# ASD2205.net
KiCad netlist of a schematic drawn in EAGLE
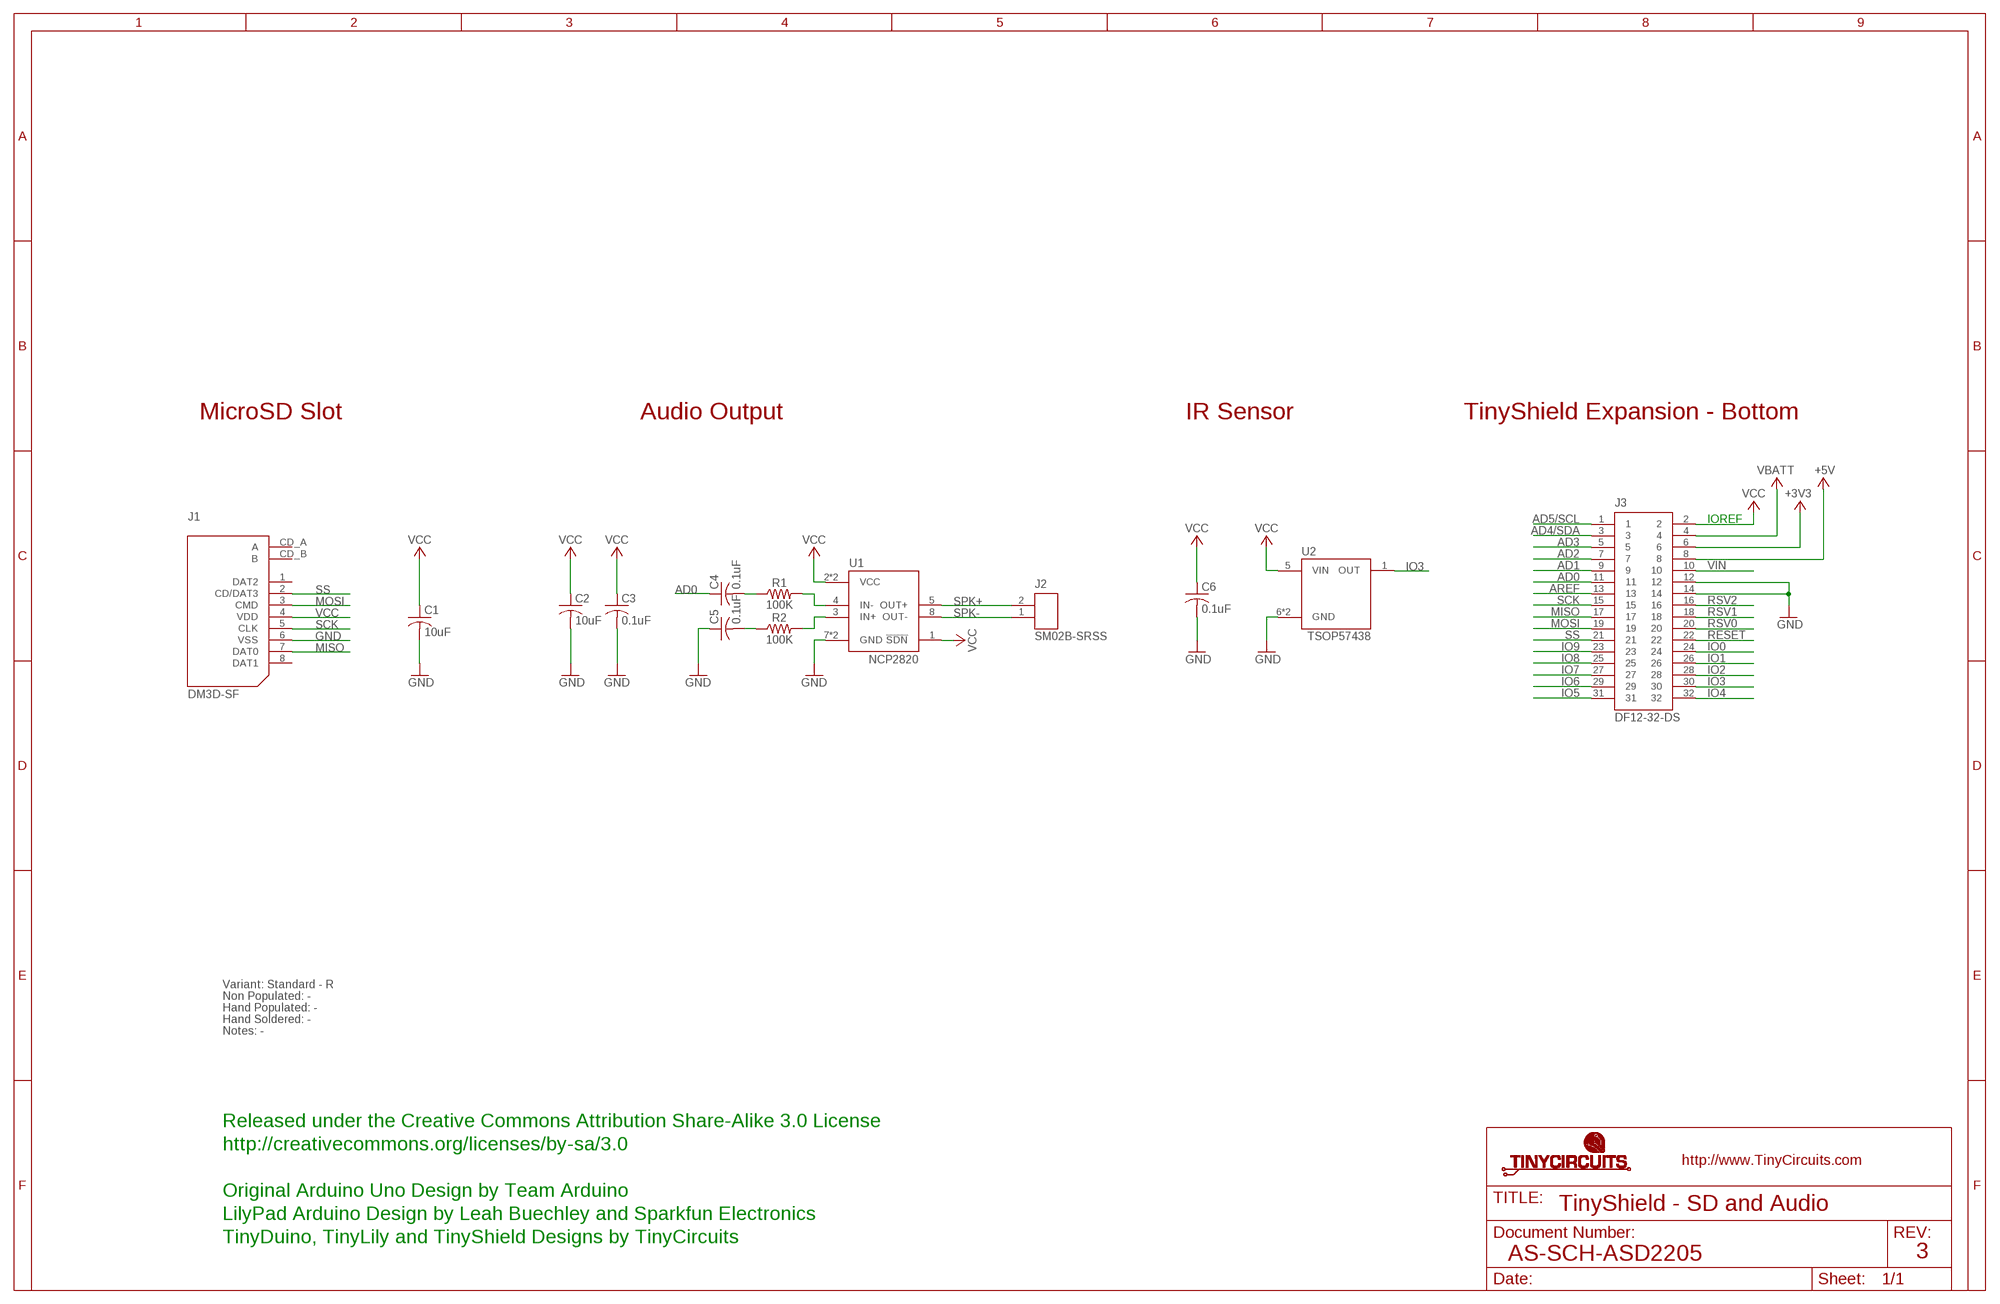
[diagram p0: schematic, sheet 1]

(export (version "E")
  (design (tool "Eeschema 10.0.6"))
  (components
    (comp (ref "C1")
      (value "10uF")
      (footprint "eagle-import:C0603")
      (fields (field (name "PARTNO") "AS-ITM-00002"))
      (libsource (lib "eagle-import") (part "AS-ITM-00002"))
    )
    (comp (ref "C2")
      (value "10uF")
      (footprint "eagle-import:C0603")
      (fields (field (name "PARTNO") "AS-ITM-00002") (field (name "PARTNO_1") "AS-ITM-00002"))
      (libsource (lib "eagle-import") (part "AS-ITM-00002"))
    )
    (comp (ref "C3")
      (value "0.1uF")
      (footprint "eagle-import:C0402")
      (fields (field (name "PARTNO") "AS-ITM-00008"))
      (libsource (lib "eagle-import") (part "AS-ITM-00008"))
    )
    (comp (ref "C4")
      (value "0.1uF")
      (footprint "eagle-import:C0402")
      (fields (field (name "PARTNO") "AS-ITM-00008"))
      (libsource (lib "eagle-import") (part "AS-ITM-00008"))
    )
    (comp (ref "C5")
      (value "0.1uF")
      (footprint "eagle-import:C0402")
      (fields (field (name "PARTNO") "AS-ITM-00008"))
      (libsource (lib "eagle-import") (part "AS-ITM-00008"))
    )
    (comp (ref "C6")
      (value "0.1uF")
      (footprint "eagle-import:C0402")
      (fields (field (name "PARTNO") "AS-ITM-00008"))
      (libsource (lib "eagle-import") (part "AS-ITM-00008"))
    )
    (comp (ref "J1")
      (value "DM3D-SF")
      (footprint "eagle-import:SD_CARD")
      (fields (field (name "PARTNO") "AS-ITM-00047"))
      (libsource (lib "eagle-import") (part "AS-ITM-00047"))
    )
    (comp (ref "J2")
      (value "SM02B-SRSS")
      (footprint "eagle-import:JST_SH_2X1")
      (fields (field (name "PARTNO") "AS-ITM-00231"))
      (libsource (lib "eagle-import") (part "AS-ITM-00231"))
    )
    (comp (ref "J3")
      (value "DF12-32-DS")
      (footprint "eagle-import:DF12-32-DS")
      (fields (field (name "PARTNO") "AS-ITM-00012") (field (name "PARTNO_1") "AS-ITM-00012"))
      (libsource (lib "eagle-import") (part "AS-ITM-00012"))
    )
    (comp (ref "R1")
      (value "100K")
      (footprint "eagle-import:0402")
      (fields (field (name "PARTNO") "AS-ITM-00004"))
      (libsource (lib "eagle-import") (part "AS-ITM-00004"))
    )
    (comp (ref "R2")
      (value "100K")
      (footprint "eagle-import:0402")
      (fields (field (name "PARTNO") "AS-ITM-00004"))
      (libsource (lib "eagle-import") (part "AS-ITM-00004"))
    )
    (comp (ref "U1")
      (value "NCP2820")
      (footprint "eagle-import:WSON-8")
      (fields (field (name "PARTNO") "AS-ITM-00370"))
      (libsource (lib "eagle-import") (part "AS-ITM-00370"))
    )
    (comp (ref "U2")
      (value "TSOP57438")
      (footprint "eagle-import:TSOP57")
      (fields (field (name "PARTNO") "AS-ITM-00360"))
      (libsource (lib "eagle-import") (part "AS-ITM-00360"))
    )
  )
  (nets
    (net (code "1") (name "+3V3") (class "Default")
      (node (ref "J3") (pin "6") (pinfunction "6_6") (pintype "bidirectional"))
    )
    (net (code "2") (name "+5V") (class "Default")
      (node (ref "J3") (pin "8") (pinfunction "8_8") (pintype "bidirectional"))
    )
    (net (code "3") (name "/AD0") (class "Default")
      (node (ref "C4") (pin "1") (pinfunction "1_1") (pintype "passive"))
      (node (ref "J3") (pin "11") (pinfunction "11_11") (pintype "bidirectional"))
    )
    (net (code "4") (name "/AD1") (class "Default")
      (node (ref "J3") (pin "9") (pinfunction "9_9") (pintype "bidirectional"))
    )
    (net (code "5") (name "/AD2") (class "Default")
      (node (ref "J3") (pin "7") (pinfunction "7_7") (pintype "bidirectional"))
    )
    (net (code "6") (name "/AD3") (class "Default")
      (node (ref "J3") (pin "5") (pinfunction "5_5") (pintype "bidirectional"))
    )
    (net (code "7") (name "/AD4{slash}SDA") (class "Default")
      (node (ref "J3") (pin "3") (pinfunction "3_3") (pintype "bidirectional"))
    )
    (net (code "8") (name "/AD5{slash}SCL") (class "Default")
      (node (ref "J3") (pin "1") (pinfunction "1_1") (pintype "bidirectional"))
    )
    (net (code "9") (name "/AREF") (class "Default")
      (node (ref "J3") (pin "13") (pinfunction "13_13") (pintype "bidirectional"))
    )
    (net (code "10") (name "/IO0") (class "Default")
      (node (ref "J3") (pin "24") (pinfunction "24_24") (pintype "bidirectional"))
    )
    (net (code "11") (name "/IO1") (class "Default")
      (node (ref "J3") (pin "26") (pinfunction "26_26") (pintype "bidirectional"))
    )
    (net (code "12") (name "/IO2") (class "Default")
      (node (ref "J3") (pin "28") (pinfunction "28_28") (pintype "bidirectional"))
    )
    (net (code "13") (name "/IO3") (class "Default")
      (node (ref "J3") (pin "30") (pinfunction "30_30") (pintype "bidirectional"))
      (node (ref "U2") (pin "1") (pinfunction "OUT_1") (pintype "bidirectional"))
    )
    (net (code "14") (name "/IO4") (class "Default")
      (node (ref "J3") (pin "32") (pinfunction "32_32") (pintype "bidirectional"))
    )
    (net (code "15") (name "/IO5") (class "Default")
      (node (ref "J3") (pin "31") (pinfunction "31_31") (pintype "bidirectional"))
    )
    (net (code "16") (name "/IO6") (class "Default")
      (node (ref "J3") (pin "29") (pinfunction "29_29") (pintype "bidirectional"))
    )
    (net (code "17") (name "/IO7") (class "Default")
      (node (ref "J3") (pin "27") (pinfunction "27_27") (pintype "bidirectional"))
    )
    (net (code "18") (name "/IO8") (class "Default")
      (node (ref "J3") (pin "25") (pinfunction "25_25") (pintype "bidirectional"))
    )
    (net (code "19") (name "/IO9") (class "Default")
      (node (ref "J3") (pin "23") (pinfunction "23_23") (pintype "bidirectional"))
    )
    (net (code "20") (name "/MISO") (class "Default")
      (node (ref "J1") (pin "7") (pinfunction "DAT0_7") (pintype "bidirectional"))
      (node (ref "J3") (pin "17") (pinfunction "17_17") (pintype "bidirectional"))
    )
    (net (code "21") (name "/MOSI") (class "Default")
      (node (ref "J1") (pin "3") (pinfunction "CMD_3") (pintype "bidirectional"))
      (node (ref "J3") (pin "19") (pinfunction "19_19") (pintype "bidirectional"))
    )
    (net (code "22") (name "/RESET") (class "Default")
      (node (ref "J3") (pin "22") (pinfunction "22_22") (pintype "bidirectional"))
    )
    (net (code "23") (name "/RSV0") (class "Default")
      (node (ref "J3") (pin "20") (pinfunction "20_20") (pintype "bidirectional"))
    )
    (net (code "24") (name "/RSV1") (class "Default")
      (node (ref "J3") (pin "18") (pinfunction "18_18") (pintype "bidirectional"))
    )
    (net (code "25") (name "/RSV2") (class "Default")
      (node (ref "J3") (pin "16") (pinfunction "16_16") (pintype "bidirectional"))
    )
    (net (code "26") (name "/SCK") (class "Default")
      (node (ref "J1") (pin "5") (pinfunction "CLK_5") (pintype "bidirectional"))
      (node (ref "J3") (pin "15") (pinfunction "15_15") (pintype "bidirectional"))
    )
    (net (code "27") (name "/SPK+") (class "Default")
      (node (ref "J2") (pin "2") (pinfunction "1_2") (pintype "bidirectional"))
      (node (ref "U1") (pin "5") (pinfunction "OUT+_5") (pintype "bidirectional"))
    )
    (net (code "28") (name "/SPK-") (class "Default")
      (node (ref "J2") (pin "1") (pinfunction "2_1") (pintype "bidirectional"))
      (node (ref "U1") (pin "8") (pinfunction "OUT-_8") (pintype "bidirectional"))
    )
    (net (code "29") (name "/SS") (class "Default")
      (node (ref "J1") (pin "2") (pinfunction "CD/DAT3_2") (pintype "bidirectional"))
      (node (ref "J3") (pin "21") (pinfunction "21_21") (pintype "bidirectional"))
    )
    (net (code "30") (name "/VIN") (class "Default")
      (node (ref "J3") (pin "10") (pinfunction "10_10") (pintype "bidirectional"))
    )
    (net (code "31") (name "GND") (class "Default")
      (node (ref "C1") (pin "2") (pinfunction "2_2") (pintype "passive"))
      (node (ref "C2") (pin "2") (pinfunction "2_2") (pintype "passive"))
      (node (ref "C3") (pin "2") (pinfunction "2_2") (pintype "passive"))
      (node (ref "C5") (pin "1") (pinfunction "1_1") (pintype "passive"))
      (node (ref "C6") (pin "2") (pinfunction "2_2") (pintype "passive"))
      (node (ref "J1") (pin "6") (pinfunction "VSS_6") (pintype "bidirectional"))
      (node (ref "J3") (pin "12") (pinfunction "12_12") (pintype "bidirectional"))
      (node (ref "J3") (pin "14") (pinfunction "14_14") (pintype "bidirectional"))
      (node (ref "U1") (pin "7") (pinfunction "GND_7") (pintype "bidirectional"))
      (node (ref "U1") (pin "9") (pinfunction "GND_9") (pintype "bidirectional"))
      (node (ref "U2") (pin "6") (pinfunction "GND_6") (pintype "bidirectional"))
      (node (ref "U2") (pin "8") (pinfunction "GND_8") (pintype "bidirectional"))
    )
    (net (code "32") (name "Net-(C4-Pad2)") (class "Default")
      (node (ref "C4") (pin "2") (pinfunction "2_2") (pintype "passive"))
      (node (ref "R1") (pin "1") (pinfunction "1_1") (pintype "passive"))
    )
    (net (code "33") (name "Net-(C5-Pad2)") (class "Default")
      (node (ref "C5") (pin "2") (pinfunction "2_2") (pintype "passive"))
      (node (ref "R2") (pin "1") (pinfunction "1_1") (pintype "passive"))
    )
    (net (code "34") (name "Net-(U1-IN+)") (class "Default")
      (node (ref "R2") (pin "2") (pinfunction "2_2") (pintype "passive"))
      (node (ref "U1") (pin "3") (pinfunction "IN+_3") (pintype "bidirectional"))
    )
    (net (code "35") (name "Net-(U1-IN-)") (class "Default")
      (node (ref "R1") (pin "2") (pinfunction "2_2") (pintype "passive"))
      (node (ref "U1") (pin "4") (pinfunction "IN-_4") (pintype "bidirectional"))
    )
    (net (code "36") (name "VBATT") (class "Default")
      (node (ref "J3") (pin "4") (pinfunction "4_4") (pintype "bidirectional"))
    )
    (net (code "37") (name "VCC") (class "Default")
      (node (ref "C1") (pin "1") (pinfunction "1_1") (pintype "passive"))
      (node (ref "C2") (pin "1") (pinfunction "1_1") (pintype "passive"))
      (node (ref "C3") (pin "1") (pinfunction "1_1") (pintype "passive"))
      (node (ref "C6") (pin "1") (pinfunction "1_1") (pintype "passive"))
      (node (ref "J1") (pin "4") (pinfunction "VDD_4") (pintype "bidirectional"))
      (node (ref "J3") (pin "2") (pinfunction "2_2") (pintype "bidirectional"))
      (node (ref "U1") (pin "1") (pinfunction "~{SDN}_1") (pintype "bidirectional"))
      (node (ref "U1") (pin "2") (pinfunction "VCC_2") (pintype "bidirectional"))
      (node (ref "U1") (pin "6") (pinfunction "VCC_6") (pintype "bidirectional"))
      (node (ref "U2") (pin "5") (pinfunction "VIN_5") (pintype "bidirectional"))
    )
    (net (code "38") (name "unconnected-(J1-A-PadCD_A)") (class "Default")
      (node (ref "J1") (pin "CD_A") (pinfunction "A_CD_A") (pintype "bidirectional"))
    )
    (net (code "39") (name "unconnected-(J1-B-PadCD_B)") (class "Default")
      (node (ref "J1") (pin "CD_B") (pinfunction "B_CD_B") (pintype "bidirectional"))
    )
    (net (code "40") (name "unconnected-(J1-DAT1-Pad8)") (class "Default")
      (node (ref "J1") (pin "8") (pinfunction "DAT1_8") (pintype "bidirectional"))
    )
    (net (code "41") (name "unconnected-(J1-DAT2-Pad1)") (class "Default")
      (node (ref "J1") (pin "1") (pinfunction "DAT2_1") (pintype "bidirectional"))
    )
  )
)
